# CoolBreaker.net
KiCad netlist of a schematic drawn in EAGLE
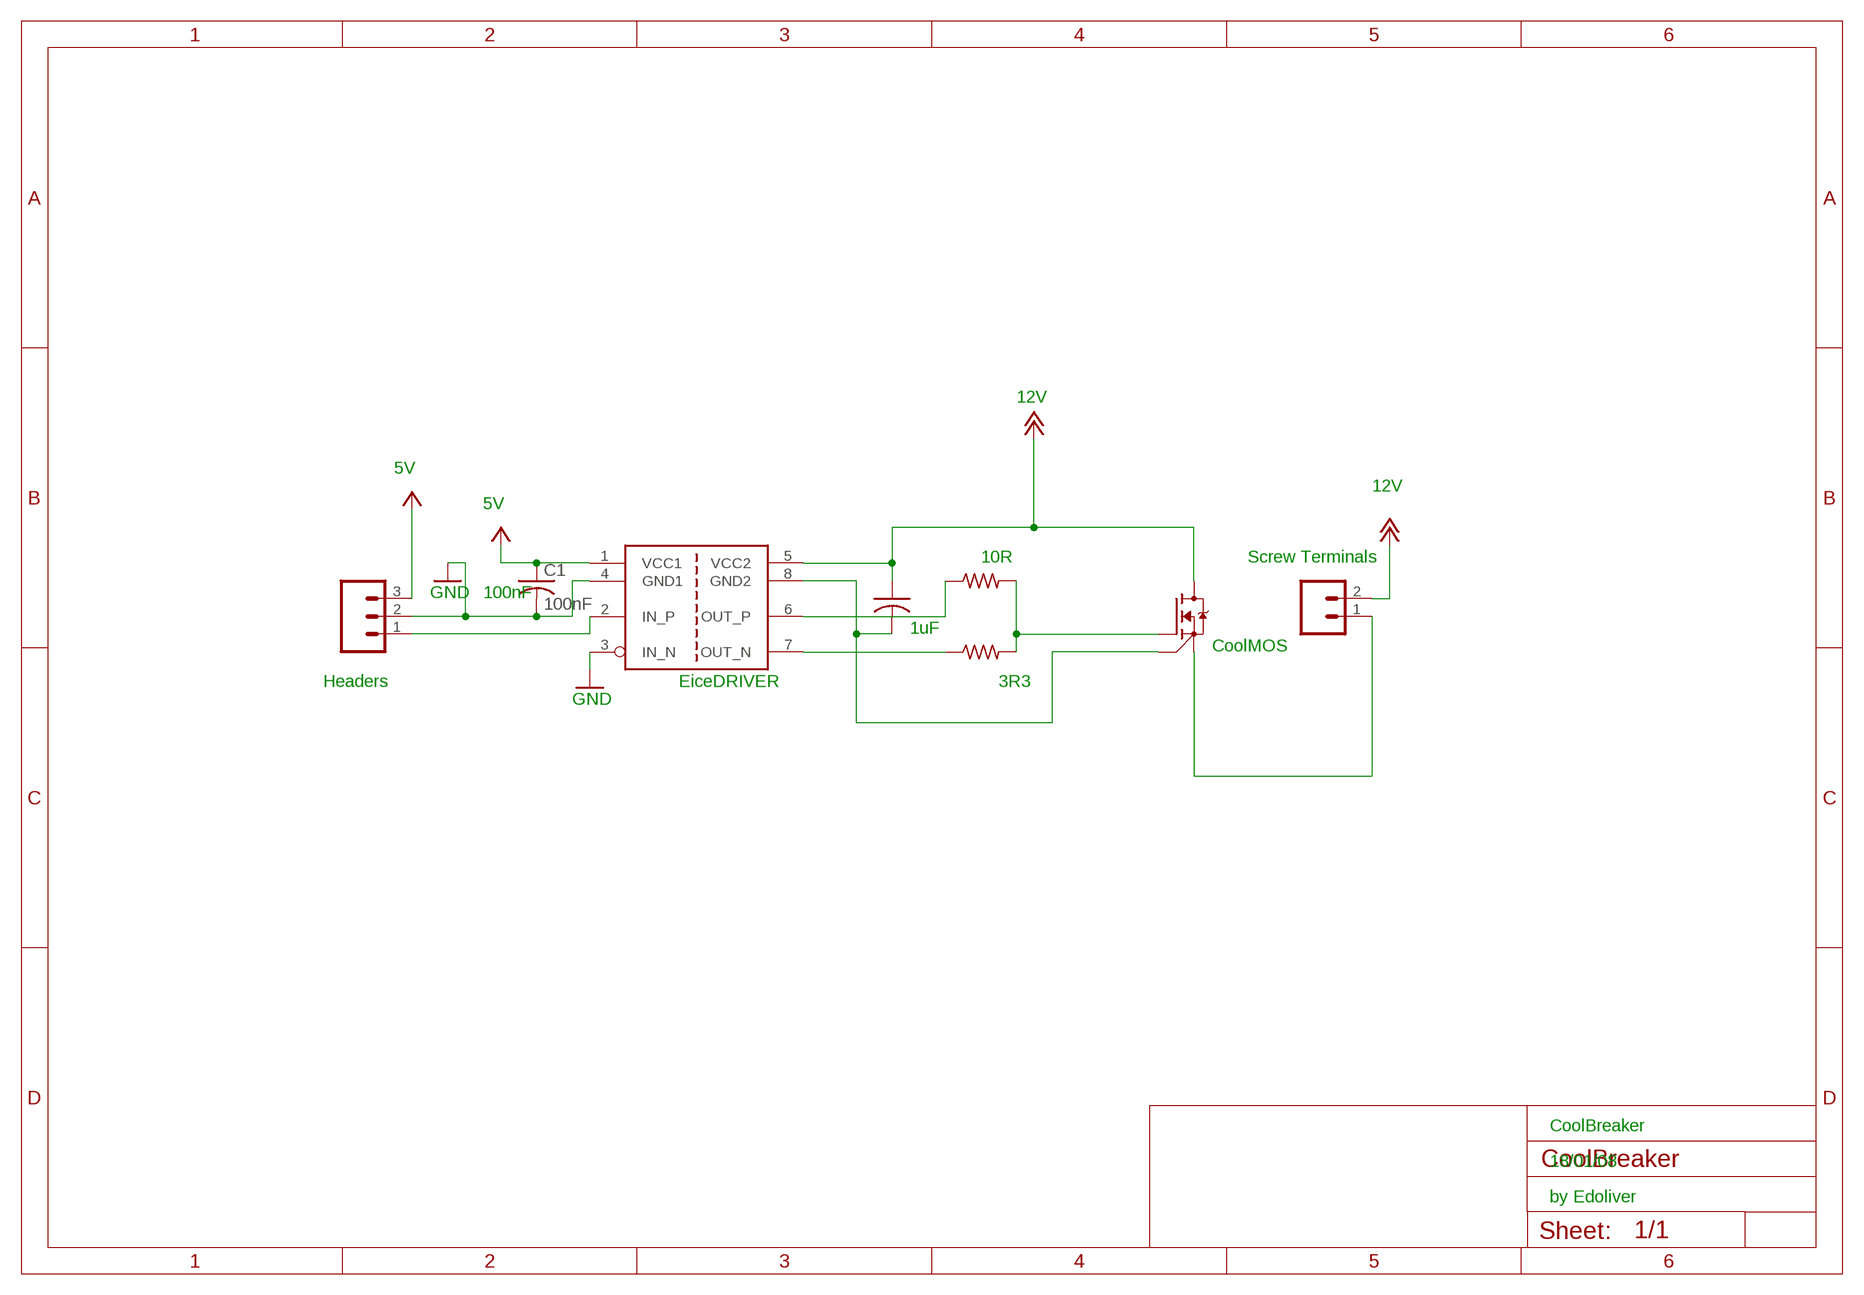
[diagram p0: schematic, sheet 1]

(export (version "E")
  (design (tool "Eeschema 10.0.6"))
  (components
    (comp (ref "C1")
      (value "100nF")
      (footprint "eagle-import:C025-024X044")
      (libsource (lib "eagle-import") (part "C-US025-024X044"))
    )
    (comp (ref "C2")
      (value "1uF")
      (footprint "eagle-import:C025-024X044")
      (libsource (lib "eagle-import") (part "C-US025-024X044"))
    )
    (comp (ref "J1")
      (value "CONN_025MM")
      (footprint "eagle-import:SCREWTERMINAL-5MM-2")
      (libsource (lib "eagle-import") (part "CONN_025MM"))
    )
    (comp (ref "J2")
      (value "455-1750-1-ND")
      (footprint "eagle-import:1X03")
      (libsource (lib "eagle-import") (part "CONN_03"))
    )
    (comp (ref "Q1")
      (value "IPT65R033G7XTMA1")
      (footprint "eagle-import:TRANS_IPT65R033G7XTMA1")
      (fields (field (name "MF") "Infineon Technologies"))
      (libsource (lib "eagle-import") (part "IPT65R033G7XTMA1"))
    )
    (comp (ref "R1")
      (value "3R3")
      (footprint "eagle-import:0204_7")
      (libsource (lib "eagle-import") (part "R-US_0204/7"))
    )
    (comp (ref "R2")
      (value "10R")
      (footprint "eagle-import:0204_7")
      (libsource (lib "eagle-import") (part "R-US_0204/7"))
    )
    (comp (ref "U1")
      (value "1EDI60N12AF")
      (footprint "eagle-import:SOIC127P600X175-8N-10")
      (libsource (lib "eagle-import") (part "1EDI60N12AF"))
    )
  )
  (nets
    (net (code "1") (name "+5V") (class "Default")
      (node (ref "C1") (pin "1") (pinfunction "1_1") (pintype "passive"))
      (node (ref "J2") (pin "3") (pinfunction "3_3") (pintype "passive"))
      (node (ref "U1") (pin "1") (pinfunction "VCC1_1") (pintype "power_in"))
    )
    (net (code "2") (name "+12V") (class "Default")
      (node (ref "C2") (pin "1") (pinfunction "1_1") (pintype "passive"))
      (node (ref "J1") (pin "2") (pinfunction "2_2") (pintype "passive"))
      (node (ref "Q1") (pin "9") (pinfunction "DRAIN_9") (pintype "passive"))
      (node (ref "U1") (pin "5") (pinfunction "VCC2_5") (pintype "power_in"))
    )
    (net (code "3") (name "GND") (class "Default")
      (node (ref "C1") (pin "2") (pinfunction "2_2") (pintype "passive"))
      (node (ref "J2") (pin "2") (pinfunction "2_2") (pintype "passive"))
      (node (ref "U1") (pin "3") (pinfunction "IN_N_3") (pintype "input"))
      (node (ref "U1") (pin "4") (pinfunction "GND1_4") (pintype "power_in"))
    )
    (net (code "4") (name "Net-(J1-Pad1)") (class "Default")
      (node (ref "J1") (pin "1") (pinfunction "1_1") (pintype "passive"))
      (node (ref "Q1") (pin "3") (pinfunction "SOURCE_3") (pintype "passive"))
      (node (ref "Q1") (pin "4") (pinfunction "SOURCE_4") (pintype "passive"))
      (node (ref "Q1") (pin "5") (pinfunction "SOURCE_5") (pintype "passive"))
      (node (ref "Q1") (pin "6") (pinfunction "SOURCE_6") (pintype "passive"))
      (node (ref "Q1") (pin "7") (pinfunction "SOURCE_7") (pintype "passive"))
      (node (ref "Q1") (pin "8") (pinfunction "SOURCE_8") (pintype "passive"))
    )
    (net (code "5") (name "Net-(Q1-DRIVER_SOURCE)") (class "Default")
      (node (ref "C2") (pin "2") (pinfunction "2_2") (pintype "passive"))
      (node (ref "Q1") (pin "2") (pinfunction "DRIVER_SOURCE_2") (pintype "passive"))
      (node (ref "U1") (pin "8") (pinfunction "GND2_8") (pintype "power_in"))
    )
    (net (code "6") (name "Net-(Q1-GATE)") (class "Default")
      (node (ref "Q1") (pin "1") (pinfunction "GATE_1") (pintype "passive"))
      (node (ref "R1") (pin "2") (pinfunction "2_2") (pintype "passive"))
      (node (ref "R2") (pin "2") (pinfunction "2_2") (pintype "passive"))
    )
    (net (code "7") (name "Net-(U1-IN_P)") (class "Default")
      (node (ref "J2") (pin "1") (pinfunction "1_1") (pintype "passive"))
      (node (ref "U1") (pin "2") (pinfunction "IN_P_2") (pintype "input"))
    )
    (net (code "8") (name "Net-(U1-OUT_N)") (class "Default")
      (node (ref "R1") (pin "1") (pinfunction "1_1") (pintype "passive"))
      (node (ref "U1") (pin "7") (pinfunction "OUT_N_7") (pintype "output"))
    )
    (net (code "9") (name "Net-(U1-OUT_P)") (class "Default")
      (node (ref "R2") (pin "1") (pinfunction "1_1") (pintype "passive"))
      (node (ref "U1") (pin "6") (pinfunction "OUT_P_6") (pintype "output"))
    )
  )
)
